# L3GD20H.net
KiCad netlist of a schematic drawn in EAGLE
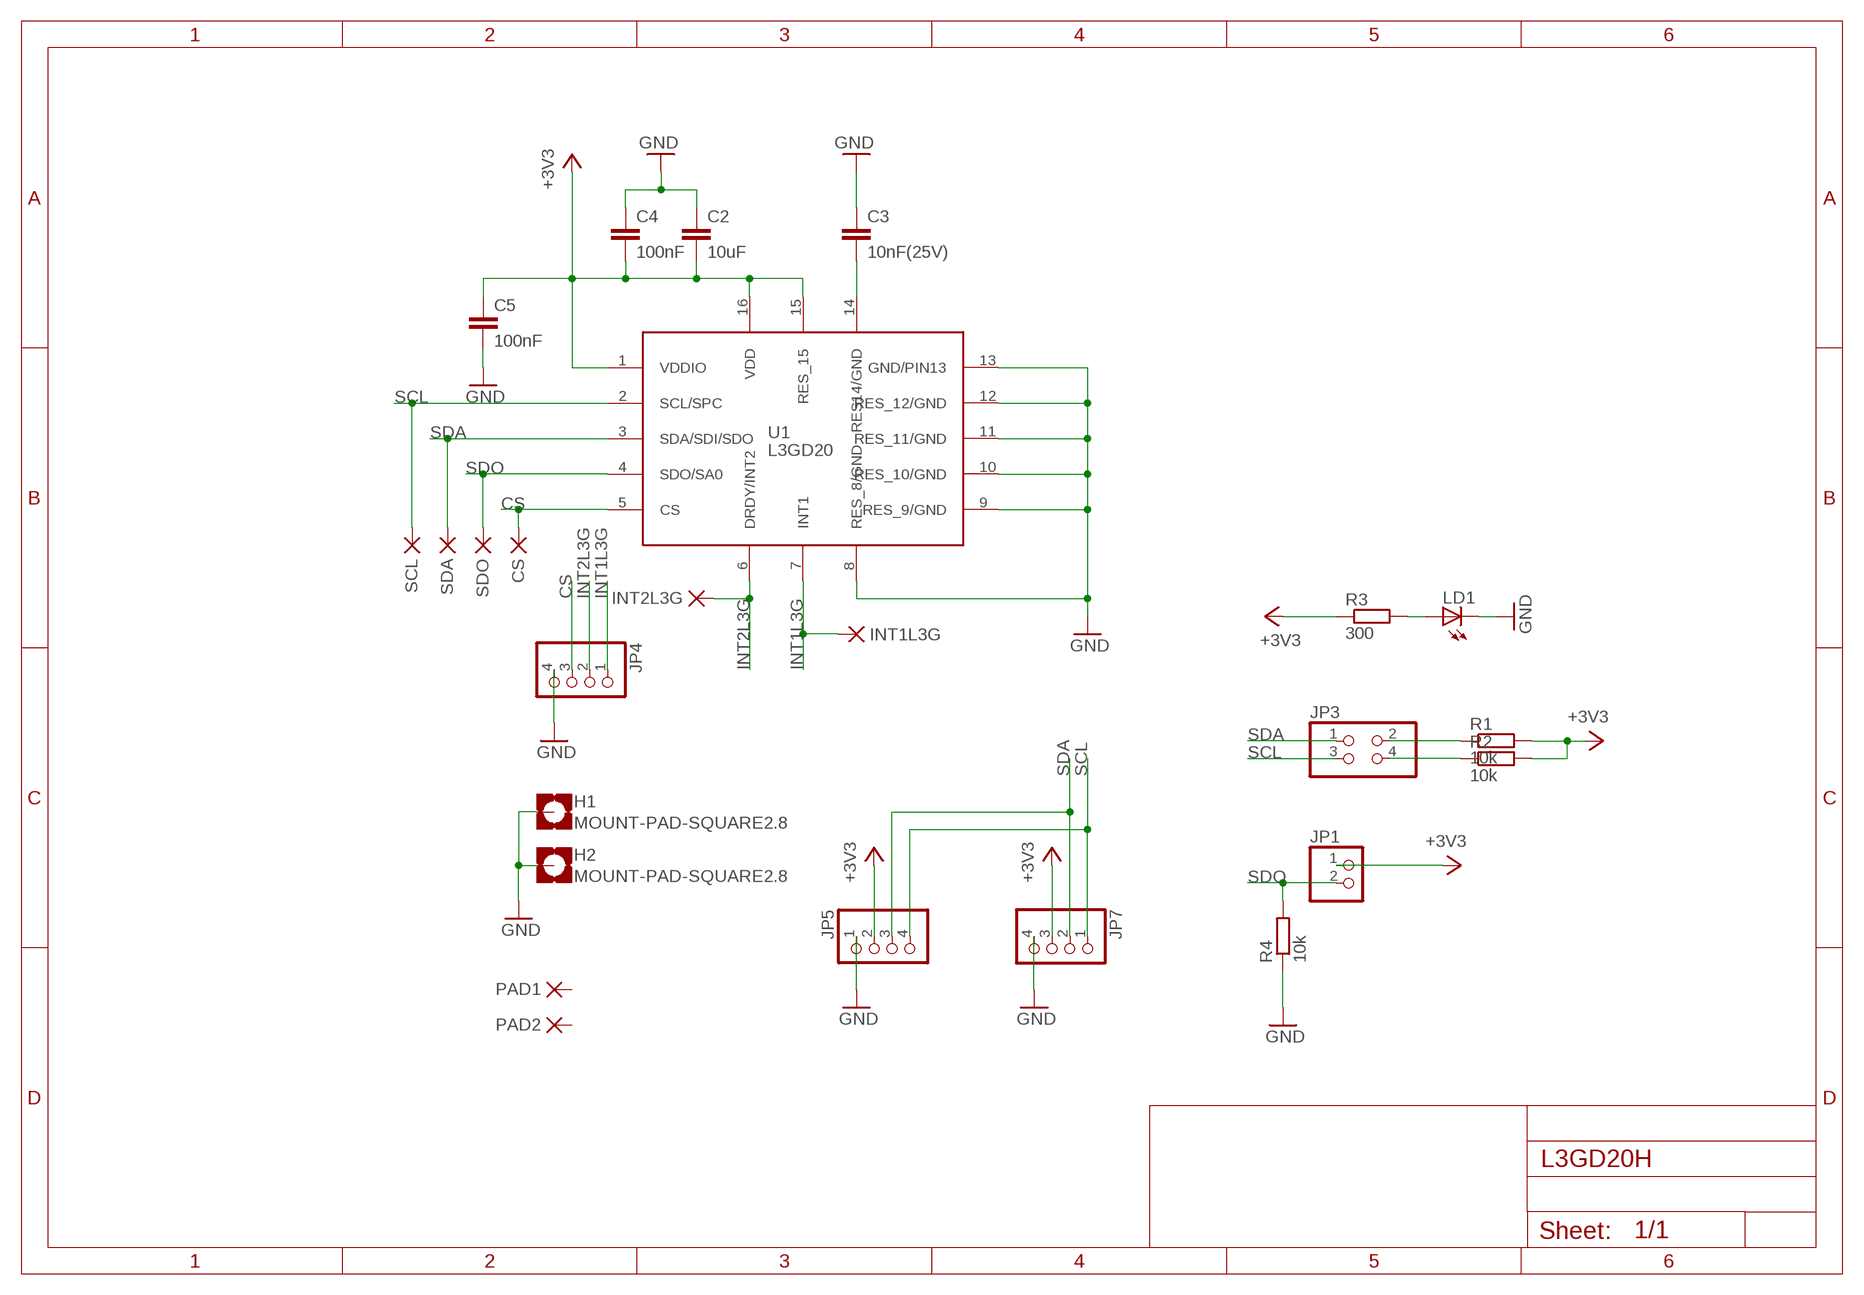
[diagram p0: schematic, sheet 1]

(export (version "E")
  (design (tool "Eeschema 10.0.6"))
  (components
    (comp (ref "C2")
      (value "10uF")
      (footprint "eagle-import:C0805")
      (libsource (lib "eagle-import") (part "C-EUC0805"))
    )
    (comp (ref "C3")
      (value "10nF(25V)")
      (footprint "eagle-import:C0805")
      (libsource (lib "eagle-import") (part "C-EUC0805"))
    )
    (comp (ref "C4")
      (value "100nF")
      (footprint "eagle-import:C0805")
      (libsource (lib "eagle-import") (part "C-EUC0805"))
    )
    (comp (ref "C5")
      (value "100nF")
      (footprint "eagle-import:C0805")
      (libsource (lib "eagle-import") (part "C-EUC0805"))
    )
    (comp (ref "CS")
      (value "PAD-SMD10R")
      (footprint "eagle-import:SMD10R")
      (libsource (lib "eagle-import") (part "PAD-SMD10R"))
    )
    (comp (ref "H1")
      (value "MOUNT-PAD-SQUARE2.8")
      (footprint "eagle-import:2,8-PAD-SQUARE")
      (libsource (lib "eagle-import") (part "MOUNT-PAD-SQUARE2.8"))
    )
    (comp (ref "H2")
      (value "MOUNT-PAD-SQUARE2.8")
      (footprint "eagle-import:2,8-PAD-SQUARE")
      (libsource (lib "eagle-import") (part "MOUNT-PAD-SQUARE2.8"))
    )
    (comp (ref "INT1L3G")
      (value "PAD-SMD10R")
      (footprint "eagle-import:SMD10R")
      (libsource (lib "eagle-import") (part "PAD-SMD10R"))
    )
    (comp (ref "INT2L3G")
      (value "PAD-SMD10R")
      (footprint "eagle-import:SMD10R")
      (libsource (lib "eagle-import") (part "PAD-SMD10R"))
    )
    (comp (ref "JP1")
      (value "PINHD-1X2")
      (footprint "eagle-import:1X02")
      (libsource (lib "eagle-import") (part "PINHD-1X2"))
    )
    (comp (ref "JP3")
      (value "PINHD-2X2_2.54")
      (footprint "eagle-import:2X02")
      (libsource (lib "eagle-import") (part "PINHD-2X2_2.54"))
    )
    (comp (ref "JP4")
      (value "PINHD-1X4")
      (footprint "eagle-import:1X04")
      (libsource (lib "eagle-import") (part "PINHD-1X4"))
    )
    (comp (ref "JP5")
      (value "PINHD-1X4_2.54-90°")
      (footprint "eagle-import:1X04_90")
      (libsource (lib "eagle-import") (part "PINHD-1X4_2.54-90°"))
    )
    (comp (ref "JP7")
      (value "PINHD-1X4_2.54-90°")
      (footprint "eagle-import:1X04_90")
      (libsource (lib "eagle-import") (part "PINHD-1X4_2.54-90°"))
    )
    (comp (ref "LD1")
      (value "LEDCHIPLED_0805")
      (footprint "eagle-import:CHIPLED_0805")
      (libsource (lib "eagle-import") (part "LEDCHIPLED_0805"))
    )
    (comp (ref "PAD1")
      (value "PAD-SMD10R")
      (footprint "eagle-import:SMD10R")
      (libsource (lib "eagle-import") (part "PAD-SMD10R"))
    )
    (comp (ref "PAD2")
      (value "PAD-SMD10R")
      (footprint "eagle-import:SMD10R")
      (libsource (lib "eagle-import") (part "PAD-SMD10R"))
    )
    (comp (ref "R1")
      (value "10k")
      (footprint "eagle-import:R0805")
      (libsource (lib "eagle-import") (part "R-EU_R0805"))
    )
    (comp (ref "R2")
      (value "10k")
      (footprint "eagle-import:R0805")
      (libsource (lib "eagle-import") (part "R-EU_R0805"))
    )
    (comp (ref "R3")
      (value "300")
      (footprint "eagle-import:R0805")
      (libsource (lib "eagle-import") (part "resistor_R-EU_R0805"))
    )
    (comp (ref "R4")
      (value "10k")
      (footprint "eagle-import:R0805")
      (libsource (lib "eagle-import") (part "R-EU_R0805"))
    )
    (comp (ref "SCL")
      (value "PAD-SMD10R")
      (footprint "eagle-import:SMD10R")
      (libsource (lib "eagle-import") (part "PAD-SMD10R"))
    )
    (comp (ref "SDA")
      (value "PAD-SMD10R")
      (footprint "eagle-import:SMD10R")
      (libsource (lib "eagle-import") (part "PAD-SMD10R"))
    )
    (comp (ref "SDO")
      (value "PAD-SMD10R")
      (footprint "eagle-import:SMD10R")
      (libsource (lib "eagle-import") (part "PAD-SMD10R"))
    )
    (comp (ref "U1")
      (value "L3GD20")
      (footprint "eagle-import:LGA16R65P4X4_400X400X160")
      (libsource (lib "eagle-import") (part "L3GD20"))
    )
  )
  (nets
    (net (code "1") (name "+3V3") (class "Default")
      (node (ref "C2") (pin "2") (pinfunction "2_2") (pintype "passive"))
      (node (ref "C4") (pin "2") (pinfunction "2_2") (pintype "passive"))
      (node (ref "C5") (pin "1") (pinfunction "1_1") (pintype "passive"))
      (node (ref "JP1") (pin "1") (pinfunction "1_1") (pintype "passive"))
      (node (ref "JP5") (pin "2") (pinfunction "2_2") (pintype "passive"))
      (node (ref "JP7") (pin "3") (pinfunction "3_3") (pintype "passive"))
      (node (ref "R1") (pin "2") (pinfunction "2_2") (pintype "passive"))
      (node (ref "R2") (pin "2") (pinfunction "2_2") (pintype "passive"))
      (node (ref "R3") (pin "1") (pinfunction "1_1") (pintype "passive"))
      (node (ref "U1") (pin "1") (pinfunction "VDDIO_1") (pintype "bidirectional"))
      (node (ref "U1") (pin "15") (pinfunction "RES_15_15") (pintype "bidirectional"))
      (node (ref "U1") (pin "16") (pinfunction "VDD_16") (pintype "bidirectional"))
    )
    (net (code "2") (name "/CS") (class "Default")
      (node (ref "CS") (pin "PAD") (pinfunction "P_PAD") (pintype "passive"))
      (node (ref "JP4") (pin "3") (pinfunction "3_3") (pintype "passive"))
      (node (ref "U1") (pin "5") (pinfunction "CS_5") (pintype "bidirectional"))
    )
    (net (code "3") (name "/INT1L3G") (class "Default")
      (node (ref "INT1L3G") (pin "PAD") (pinfunction "P_PAD") (pintype "passive"))
      (node (ref "JP4") (pin "1") (pinfunction "1_1") (pintype "passive"))
      (node (ref "U1") (pin "7") (pinfunction "INT1_7") (pintype "bidirectional"))
    )
    (net (code "4") (name "/INT2L3G") (class "Default")
      (node (ref "INT2L3G") (pin "PAD") (pinfunction "P_PAD") (pintype "passive"))
      (node (ref "JP4") (pin "2") (pinfunction "2_2") (pintype "passive"))
      (node (ref "U1") (pin "6") (pinfunction "DRDY/INT2_6") (pintype "bidirectional"))
    )
    (net (code "5") (name "/SCL") (class "Default")
      (node (ref "JP3") (pin "3") (pinfunction "3_3") (pintype "passive"))
      (node (ref "JP5") (pin "4") (pinfunction "4_4") (pintype "passive"))
      (node (ref "JP7") (pin "1") (pinfunction "1_1") (pintype "passive"))
      (node (ref "SCL") (pin "PAD") (pinfunction "P_PAD") (pintype "passive"))
      (node (ref "U1") (pin "2") (pinfunction "SCL/SPC_2") (pintype "bidirectional"))
    )
    (net (code "6") (name "/SDA") (class "Default")
      (node (ref "JP3") (pin "1") (pinfunction "1_1") (pintype "passive"))
      (node (ref "JP5") (pin "3") (pinfunction "3_3") (pintype "passive"))
      (node (ref "JP7") (pin "2") (pinfunction "2_2") (pintype "passive"))
      (node (ref "SDA") (pin "PAD") (pinfunction "P_PAD") (pintype "passive"))
      (node (ref "U1") (pin "3") (pinfunction "SDA/SDI/SDO_3") (pintype "bidirectional"))
    )
    (net (code "7") (name "/SDO") (class "Default")
      (node (ref "JP1") (pin "2") (pinfunction "2_2") (pintype "passive"))
      (node (ref "R4") (pin "2") (pinfunction "2_2") (pintype "passive"))
      (node (ref "SDO") (pin "PAD") (pinfunction "P_PAD") (pintype "passive"))
      (node (ref "U1") (pin "4") (pinfunction "SDO/SA0_4") (pintype "bidirectional"))
    )
    (net (code "8") (name "GND") (class "Default")
      (node (ref "C2") (pin "1") (pinfunction "1_1") (pintype "passive"))
      (node (ref "C3") (pin "1") (pinfunction "1_1") (pintype "passive"))
      (node (ref "C4") (pin "1") (pinfunction "1_1") (pintype "passive"))
      (node (ref "C5") (pin "2") (pinfunction "2_2") (pintype "passive"))
      (node (ref "H1") (pin "B2,8") (pinfunction "MOUNT_B2,8") (pintype "passive"))
      (node (ref "H2") (pin "B2,8") (pinfunction "MOUNT_B2,8") (pintype "passive"))
      (node (ref "JP4") (pin "4") (pinfunction "4_4") (pintype "passive"))
      (node (ref "JP5") (pin "1") (pinfunction "1_1") (pintype "passive"))
      (node (ref "JP7") (pin "4") (pinfunction "4_4") (pintype "passive"))
      (node (ref "LD1") (pin "C") (pinfunction "C_C") (pintype "passive"))
      (node (ref "R4") (pin "1") (pinfunction "1_1") (pintype "passive"))
      (node (ref "U1") (pin "10") (pinfunction "RES_10/GND_10") (pintype "bidirectional"))
      (node (ref "U1") (pin "11") (pinfunction "RES_11/GND_11") (pintype "bidirectional"))
      (node (ref "U1") (pin "12") (pinfunction "RES_12/GND_12") (pintype "bidirectional"))
      (node (ref "U1") (pin "13") (pinfunction "GND/PIN13_13") (pintype "bidirectional"))
      (node (ref "U1") (pin "8") (pinfunction "RES_8/GND_8") (pintype "bidirectional"))
      (node (ref "U1") (pin "9") (pinfunction "RES_9/GND_9") (pintype "bidirectional"))
    )
    (net (code "9") (name "Net-(JP3-Pad2)") (class "Default")
      (node (ref "JP3") (pin "2") (pinfunction "2_2") (pintype "passive"))
      (node (ref "R1") (pin "1") (pinfunction "1_1") (pintype "passive"))
    )
    (net (code "10") (name "Net-(JP3-Pad4)") (class "Default")
      (node (ref "JP3") (pin "4") (pinfunction "4_4") (pintype "passive"))
      (node (ref "R2") (pin "1") (pinfunction "1_1") (pintype "passive"))
    )
    (net (code "11") (name "Net-(LD1-PadA)") (class "Default")
      (node (ref "LD1") (pin "A") (pinfunction "A_A") (pintype "passive"))
      (node (ref "R3") (pin "2") (pinfunction "2_2") (pintype "passive"))
    )
    (net (code "12") (name "Net-(U1-RES14{slash}GND)") (class "Default")
      (node (ref "C3") (pin "2") (pinfunction "2_2") (pintype "passive"))
      (node (ref "U1") (pin "14") (pinfunction "RES14/GND_14") (pintype "bidirectional"))
    )
    (net (code "13") (name "unconnected-(PAD1-P-PadPAD)") (class "Default")
      (node (ref "PAD1") (pin "PAD") (pinfunction "P_PAD") (pintype "passive"))
    )
    (net (code "14") (name "unconnected-(PAD2-P-PadPAD)") (class "Default")
      (node (ref "PAD2") (pin "PAD") (pinfunction "P_PAD") (pintype "passive"))
    )
  )
)
